# 14_-FPGA_Bank_7_Interface.net
KiCad netlist of a schematic drawn in Altium Designer
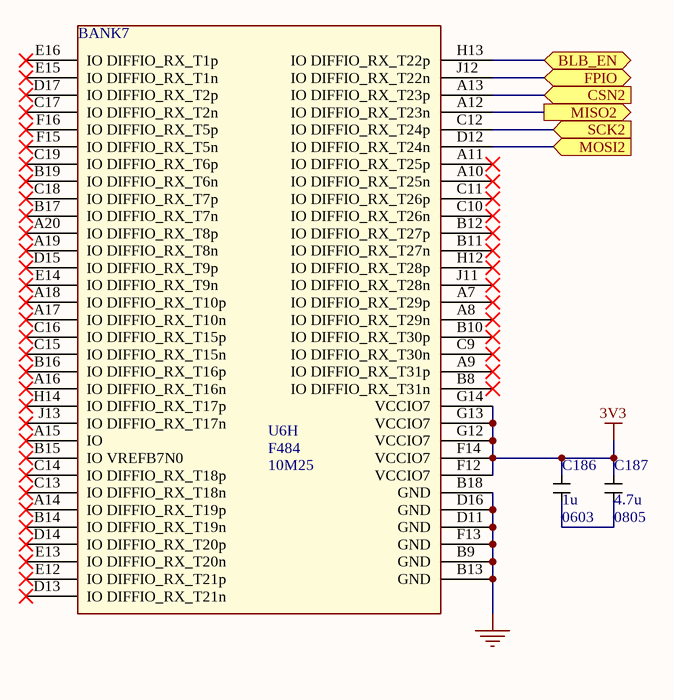
[diagram p0: [14]-FPGA_Bank_7_Interface.SchDoc]

(export (version "E")
  (design (tool "Eeschema 10.0.6"))
  (components
    (comp (ref "C186")
      (value "1u")
      (footprint "*0603")
      (fields (field (name "PCB LAYER:") "0603"))
      (libsource (lib "0603YC105KAT2A") (part "Component_1"))
    )
    (comp (ref "C187")
      (value "4.7u")
      (footprint "*CAPC2013X140N")
      (fields (field (name "PCB PACKAGE") "0805"))
      (libsource (lib "08053D475KAT2A") (part "Component_1"))
    )
    (comp (ref "U6")
      (value "10M25")
      (footprint "*BGA484C100P22X22_2300X2300X200N")
      (fields (field (name "PART NO.") "10M25DAF484I7G") (field (name "PACKAGE TYPE") "F484"))
      (libsource (lib "10M25DAF484I7G") (part "Component_1"))
    )
  )
  (nets
    (net (code "1") (name "/BLB_EN") (class "Default")
      (node (ref "U6") (pin "H13") (pinfunction "IO_DIFFIO_RX_T22p_H13") (pintype "passive"))
    )
    (net (code "2") (name "/CSN2") (class "Default")
      (node (ref "U6") (pin "A13") (pinfunction "IO_DIFFIO_RX_T23p_A13") (pintype "passive"))
    )
    (net (code "3") (name "/FPIO") (class "Default")
      (node (ref "U6") (pin "J12") (pinfunction "IO_DIFFIO_RX_T22n_J12") (pintype "passive"))
    )
    (net (code "4") (name "/MISO2") (class "Default")
      (node (ref "U6") (pin "A12") (pinfunction "IO_DIFFIO_RX_T23n_A12") (pintype "passive"))
    )
    (net (code "5") (name "/MOSI2") (class "Default")
      (node (ref "U6") (pin "D12") (pinfunction "IO_DIFFIO_RX_T24n_D12") (pintype "passive"))
    )
    (net (code "6") (name "/SCK2") (class "Default")
      (node (ref "U6") (pin "C12") (pinfunction "IO_DIFFIO_RX_T24p_C12") (pintype "passive"))
    )
    (net (code "7") (name "3V3") (class "Default")
      (node (ref "C186") (pin "2") (pinfunction "2_2") (pintype "passive"))
      (node (ref "C187") (pin "2") (pinfunction "2_2") (pintype "passive"))
      (node (ref "U6") (pin "F12") (pinfunction "VCCIO7_F12") (pintype "passive"))
      (node (ref "U6") (pin "F14") (pinfunction "VCCIO7_F14") (pintype "passive"))
      (node (ref "U6") (pin "G12") (pinfunction "VCCIO7_G12") (pintype "passive"))
      (node (ref "U6") (pin "G13") (pinfunction "VCCIO7_G13") (pintype "passive"))
      (node (ref "U6") (pin "G14") (pinfunction "VCCIO7_G14") (pintype "passive"))
    )
    (net (code "8") (name "GND") (class "Default")
      (node (ref "U6") (pin "B13") (pinfunction "GND_B13") (pintype "passive"))
      (node (ref "U6") (pin "B18") (pinfunction "GND_B18") (pintype "passive"))
      (node (ref "U6") (pin "B9") (pinfunction "GND_B9") (pintype "passive"))
      (node (ref "U6") (pin "D11") (pinfunction "GND_D11") (pintype "passive"))
      (node (ref "U6") (pin "D16") (pinfunction "GND_D16") (pintype "passive"))
      (node (ref "U6") (pin "F13") (pinfunction "GND_F13") (pintype "passive"))
    )
    (net (code "9") (name "Net-(C186-Pad1)") (class "Default")
      (node (ref "C186") (pin "1") (pinfunction "1_1") (pintype "passive"))
      (node (ref "C187") (pin "1") (pinfunction "1_1") (pintype "passive"))
    )
    (net (code "10") (name "unconnected-(U6H-IO-PadA15)") (class "Default")
      (node (ref "U6") (pin "A15") (pinfunction "IO_A15") (pintype "passive+no_connect"))
    )
    (net (code "11") (name "unconnected-(U6H-IO_DIFFIO_RX_T1n-PadE15)") (class "Default")
      (node (ref "U6") (pin "E15") (pinfunction "IO_DIFFIO_RX_T1n_E15") (pintype "passive+no_connect"))
    )
    (net (code "12") (name "unconnected-(U6H-IO_DIFFIO_RX_T1p-PadE16)") (class "Default")
      (node (ref "U6") (pin "E16") (pinfunction "IO_DIFFIO_RX_T1p_E16") (pintype "passive+no_connect"))
    )
    (net (code "13") (name "unconnected-(U6H-IO_DIFFIO_RX_T2n-PadC17)") (class "Default")
      (node (ref "U6") (pin "C17") (pinfunction "IO_DIFFIO_RX_T2n_C17") (pintype "passive+no_connect"))
    )
    (net (code "14") (name "unconnected-(U6H-IO_DIFFIO_RX_T2p-PadD17)") (class "Default")
      (node (ref "U6") (pin "D17") (pinfunction "IO_DIFFIO_RX_T2p_D17") (pintype "passive+no_connect"))
    )
    (net (code "15") (name "unconnected-(U6H-IO_DIFFIO_RX_T5n-PadF15)") (class "Default")
      (node (ref "U6") (pin "F15") (pinfunction "IO_DIFFIO_RX_T5n_F15") (pintype "passive+no_connect"))
    )
    (net (code "16") (name "unconnected-(U6H-IO_DIFFIO_RX_T5p-PadF16)") (class "Default")
      (node (ref "U6") (pin "F16") (pinfunction "IO_DIFFIO_RX_T5p_F16") (pintype "passive+no_connect"))
    )
    (net (code "17") (name "unconnected-(U6H-IO_DIFFIO_RX_T6n-PadB19)") (class "Default")
      (node (ref "U6") (pin "B19") (pinfunction "IO_DIFFIO_RX_T6n_B19") (pintype "passive+no_connect"))
    )
    (net (code "18") (name "unconnected-(U6H-IO_DIFFIO_RX_T6p-PadC19)") (class "Default")
      (node (ref "U6") (pin "C19") (pinfunction "IO_DIFFIO_RX_T6p_C19") (pintype "passive+no_connect"))
    )
    (net (code "19") (name "unconnected-(U6H-IO_DIFFIO_RX_T7n-PadB17)") (class "Default")
      (node (ref "U6") (pin "B17") (pinfunction "IO_DIFFIO_RX_T7n_B17") (pintype "passive+no_connect"))
    )
    (net (code "20") (name "unconnected-(U6H-IO_DIFFIO_RX_T7p-PadC18)") (class "Default")
      (node (ref "U6") (pin "C18") (pinfunction "IO_DIFFIO_RX_T7p_C18") (pintype "passive+no_connect"))
    )
    (net (code "21") (name "unconnected-(U6H-IO_DIFFIO_RX_T8n-PadA19)") (class "Default")
      (node (ref "U6") (pin "A19") (pinfunction "IO_DIFFIO_RX_T8n_A19") (pintype "passive+no_connect"))
    )
    (net (code "22") (name "unconnected-(U6H-IO_DIFFIO_RX_T8p-PadA20)") (class "Default")
      (node (ref "U6") (pin "A20") (pinfunction "IO_DIFFIO_RX_T8p_A20") (pintype "passive+no_connect"))
    )
    (net (code "23") (name "unconnected-(U6H-IO_DIFFIO_RX_T9n-PadE14)") (class "Default")
      (node (ref "U6") (pin "E14") (pinfunction "IO_DIFFIO_RX_T9n_E14") (pintype "passive+no_connect"))
    )
    (net (code "24") (name "unconnected-(U6H-IO_DIFFIO_RX_T9p-PadD15)") (class "Default")
      (node (ref "U6") (pin "D15") (pinfunction "IO_DIFFIO_RX_T9p_D15") (pintype "passive+no_connect"))
    )
    (net (code "25") (name "unconnected-(U6H-IO_DIFFIO_RX_T10n-PadA17)") (class "Default")
      (node (ref "U6") (pin "A17") (pinfunction "IO_DIFFIO_RX_T10n_A17") (pintype "passive+no_connect"))
    )
    (net (code "26") (name "unconnected-(U6H-IO_DIFFIO_RX_T10p-PadA18)") (class "Default")
      (node (ref "U6") (pin "A18") (pinfunction "IO_DIFFIO_RX_T10p_A18") (pintype "passive+no_connect"))
    )
    (net (code "27") (name "unconnected-(U6H-IO_DIFFIO_RX_T15n-PadC15)") (class "Default")
      (node (ref "U6") (pin "C15") (pinfunction "IO_DIFFIO_RX_T15n_C15") (pintype "passive+no_connect"))
    )
    (net (code "28") (name "unconnected-(U6H-IO_DIFFIO_RX_T15p-PadC16)") (class "Default")
      (node (ref "U6") (pin "C16") (pinfunction "IO_DIFFIO_RX_T15p_C16") (pintype "passive+no_connect"))
    )
    (net (code "29") (name "unconnected-(U6H-IO_DIFFIO_RX_T16n-PadA16)") (class "Default")
      (node (ref "U6") (pin "A16") (pinfunction "IO_DIFFIO_RX_T16n_A16") (pintype "passive+no_connect"))
    )
    (net (code "30") (name "unconnected-(U6H-IO_DIFFIO_RX_T16p-PadB16)") (class "Default")
      (node (ref "U6") (pin "B16") (pinfunction "IO_DIFFIO_RX_T16p_B16") (pintype "passive+no_connect"))
    )
    (net (code "31") (name "unconnected-(U6H-IO_DIFFIO_RX_T17n-PadJ13)") (class "Default")
      (node (ref "U6") (pin "J13") (pinfunction "IO_DIFFIO_RX_T17n_J13") (pintype "passive+no_connect"))
    )
    (net (code "32") (name "unconnected-(U6H-IO_DIFFIO_RX_T17p-PadH14)") (class "Default")
      (node (ref "U6") (pin "H14") (pinfunction "IO_DIFFIO_RX_T17p_H14") (pintype "passive+no_connect"))
    )
    (net (code "33") (name "unconnected-(U6H-IO_DIFFIO_RX_T18n-PadC13)") (class "Default")
      (node (ref "U6") (pin "C13") (pinfunction "IO_DIFFIO_RX_T18n_C13") (pintype "passive+no_connect"))
    )
    (net (code "34") (name "unconnected-(U6H-IO_DIFFIO_RX_T18p-PadC14)") (class "Default")
      (node (ref "U6") (pin "C14") (pinfunction "IO_DIFFIO_RX_T18p_C14") (pintype "passive+no_connect"))
    )
    (net (code "35") (name "unconnected-(U6H-IO_DIFFIO_RX_T19n-PadB14)") (class "Default")
      (node (ref "U6") (pin "B14") (pinfunction "IO_DIFFIO_RX_T19n_B14") (pintype "passive+no_connect"))
    )
    (net (code "36") (name "unconnected-(U6H-IO_DIFFIO_RX_T19p-PadA14)") (class "Default")
      (node (ref "U6") (pin "A14") (pinfunction "IO_DIFFIO_RX_T19p_A14") (pintype "passive+no_connect"))
    )
    (net (code "37") (name "unconnected-(U6H-IO_DIFFIO_RX_T20n-PadE13)") (class "Default")
      (node (ref "U6") (pin "E13") (pinfunction "IO_DIFFIO_RX_T20n_E13") (pintype "passive+no_connect"))
    )
    (net (code "38") (name "unconnected-(U6H-IO_DIFFIO_RX_T20p-PadD14)") (class "Default")
      (node (ref "U6") (pin "D14") (pinfunction "IO_DIFFIO_RX_T20p_D14") (pintype "passive+no_connect"))
    )
    (net (code "39") (name "unconnected-(U6H-IO_DIFFIO_RX_T21n-PadD13)") (class "Default")
      (node (ref "U6") (pin "D13") (pinfunction "IO_DIFFIO_RX_T21n_D13") (pintype "passive+no_connect"))
    )
    (net (code "40") (name "unconnected-(U6H-IO_DIFFIO_RX_T21p-PadE12)") (class "Default")
      (node (ref "U6") (pin "E12") (pinfunction "IO_DIFFIO_RX_T21p_E12") (pintype "passive+no_connect"))
    )
    (net (code "41") (name "unconnected-(U6H-IO_DIFFIO_RX_T25n-PadA10)") (class "Default")
      (node (ref "U6") (pin "A10") (pinfunction "IO_DIFFIO_RX_T25n_A10") (pintype "passive+no_connect"))
    )
    (net (code "42") (name "unconnected-(U6H-IO_DIFFIO_RX_T25p-PadA11)") (class "Default")
      (node (ref "U6") (pin "A11") (pinfunction "IO_DIFFIO_RX_T25p_A11") (pintype "passive+no_connect"))
    )
    (net (code "43") (name "unconnected-(U6H-IO_DIFFIO_RX_T26n-PadC10)") (class "Default")
      (node (ref "U6") (pin "C10") (pinfunction "IO_DIFFIO_RX_T26n_C10") (pintype "passive+no_connect"))
    )
    (net (code "44") (name "unconnected-(U6H-IO_DIFFIO_RX_T26p-PadC11)") (class "Default")
      (node (ref "U6") (pin "C11") (pinfunction "IO_DIFFIO_RX_T26p_C11") (pintype "passive+no_connect"))
    )
    (net (code "45") (name "unconnected-(U6H-IO_DIFFIO_RX_T27n-PadB11)") (class "Default")
      (node (ref "U6") (pin "B11") (pinfunction "IO_DIFFIO_RX_T27n_B11") (pintype "passive+no_connect"))
    )
    (net (code "46") (name "unconnected-(U6H-IO_DIFFIO_RX_T27p-PadB12)") (class "Default")
      (node (ref "U6") (pin "B12") (pinfunction "IO_DIFFIO_RX_T27p_B12") (pintype "passive+no_connect"))
    )
    (net (code "47") (name "unconnected-(U6H-IO_DIFFIO_RX_T28n-PadJ11)") (class "Default")
      (node (ref "U6") (pin "J11") (pinfunction "IO_DIFFIO_RX_T28n_J11") (pintype "passive+no_connect"))
    )
    (net (code "48") (name "unconnected-(U6H-IO_DIFFIO_RX_T28p-PadH12)") (class "Default")
      (node (ref "U6") (pin "H12") (pinfunction "IO_DIFFIO_RX_T28p_H12") (pintype "passive+no_connect"))
    )
    (net (code "49") (name "unconnected-(U6H-IO_DIFFIO_RX_T29n-PadA8)") (class "Default")
      (node (ref "U6") (pin "A8") (pinfunction "IO_DIFFIO_RX_T29n_A8") (pintype "passive+no_connect"))
    )
    (net (code "50") (name "unconnected-(U6H-IO_DIFFIO_RX_T29p-PadA7)") (class "Default")
      (node (ref "U6") (pin "A7") (pinfunction "IO_DIFFIO_RX_T29p_A7") (pintype "passive+no_connect"))
    )
    (net (code "51") (name "unconnected-(U6H-IO_DIFFIO_RX_T30n-PadC9)") (class "Default")
      (node (ref "U6") (pin "C9") (pinfunction "IO_DIFFIO_RX_T30n_C9") (pintype "passive+no_connect"))
    )
    (net (code "52") (name "unconnected-(U6H-IO_DIFFIO_RX_T30p-PadB10)") (class "Default")
      (node (ref "U6") (pin "B10") (pinfunction "IO_DIFFIO_RX_T30p_B10") (pintype "passive+no_connect"))
    )
    (net (code "53") (name "unconnected-(U6H-IO_DIFFIO_RX_T31n-PadB8)") (class "Default")
      (node (ref "U6") (pin "B8") (pinfunction "IO_DIFFIO_RX_T31n_B8") (pintype "passive+no_connect"))
    )
    (net (code "54") (name "unconnected-(U6H-IO_DIFFIO_RX_T31p-PadA9)") (class "Default")
      (node (ref "U6") (pin "A9") (pinfunction "IO_DIFFIO_RX_T31p_A9") (pintype "passive+no_connect"))
    )
    (net (code "55") (name "unconnected-(U6H-IO_VREFB7N0-PadB15)") (class "Default")
      (node (ref "U6") (pin "B15") (pinfunction "IO_VREFB7N0_B15") (pintype "passive+no_connect"))
    )
  )
)
